# fen.net
KiCad netlist of a schematic drawn in EAGLE
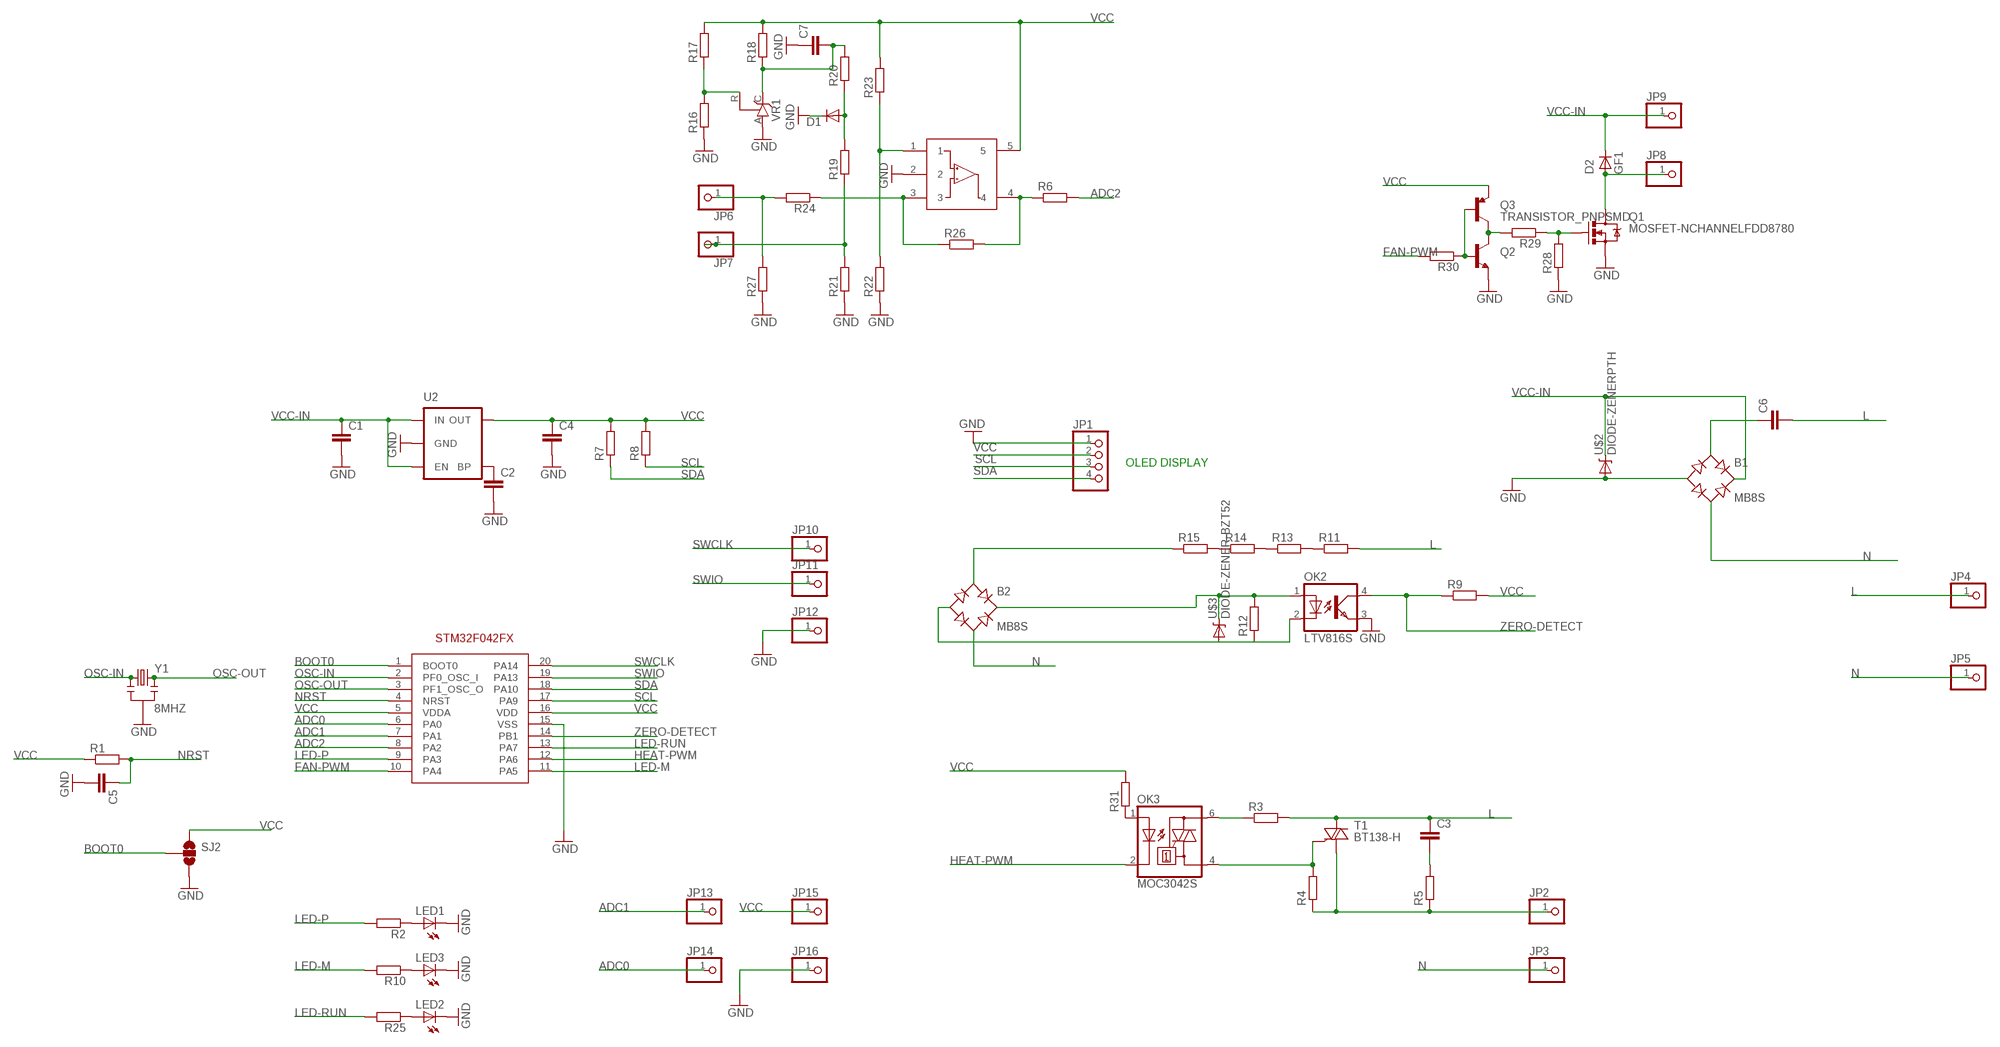
[diagram p0: schematic, sheet 1]

(export (version "E")
  (design (tool "Eeschema 10.0.6"))
  (components
    (comp (ref "B1")
      (value "MB8S")
      (footprint "eagle-import:SOIC-4")
      (libsource (lib "eagle-import") (part "MBS8"))
    )
    (comp (ref "B2")
      (value "MB8S")
      (footprint "eagle-import:SOIC-4")
      (libsource (lib "eagle-import") (part "MBS8"))
    )
    (comp (ref "C1")
      (value "C-EUC0805")
      (footprint "eagle-import:C0805")
      (libsource (lib "eagle-import") (part "C-EUC0805"))
    )
    (comp (ref "C2")
      (value "C-EUC0603")
      (footprint "eagle-import:C0603")
      (libsource (lib "eagle-import") (part "C-EUC0603"))
    )
    (comp (ref "C3")
      (value "C-EUC1206")
      (footprint "eagle-import:C1206")
      (libsource (lib "eagle-import") (part "C-EUC1206"))
    )
    (comp (ref "C4")
      (value "C-EUC0805")
      (footprint "eagle-import:C0805")
      (libsource (lib "eagle-import") (part "C-EUC0805"))
    )
    (comp (ref "C5")
      (value "C-EUC0603")
      (footprint "eagle-import:C0603")
      (libsource (lib "eagle-import") (part "C-EUC0603"))
    )
    (comp (ref "C6")
      (value "C-EU150-072X183")
      (footprint "eagle-import:C150-072X183")
      (libsource (lib "eagle-import") (part "C-EU150-072X183"))
    )
    (comp (ref "C7")
      (value "C-EUC0805")
      (footprint "eagle-import:C0805")
      (libsource (lib "eagle-import") (part "C-EUC0805"))
    )
    (comp (ref "D1")
      (value "DIODE1N4148")
      (footprint "eagle-import:DIODE-1N4148")
      (libsource (lib "eagle-import") (part "DIODE1N4148"))
    )
    (comp (ref "D2")
      (value "GF1")
      (footprint "eagle-import:SMA-DO214AC")
      (libsource (lib "eagle-import") (part "GF1"))
    )
    (comp (ref "JP1")
      (value "PINHD-1X4")
      (footprint "eagle-import:1X04")
      (libsource (lib "eagle-import") (part "PINHD-1X4"))
    )
    (comp (ref "JP2")
      (value "PINHD-1X1")
      (footprint "eagle-import:1X01")
      (libsource (lib "eagle-import") (part "PINHD-1X1"))
    )
    (comp (ref "JP3")
      (value "PINHD-1X1")
      (footprint "eagle-import:1X01")
      (libsource (lib "eagle-import") (part "PINHD-1X1"))
    )
    (comp (ref "JP4")
      (value "PINHD-1X1")
      (footprint "eagle-import:1X01")
      (libsource (lib "eagle-import") (part "PINHD-1X1"))
    )
    (comp (ref "JP5")
      (value "PINHD-1X1")
      (footprint "eagle-import:1X01")
      (libsource (lib "eagle-import") (part "PINHD-1X1"))
    )
    (comp (ref "JP6")
      (value "PINHD-1X1")
      (footprint "eagle-import:1X01")
      (libsource (lib "eagle-import") (part "PINHD-1X1"))
    )
    (comp (ref "JP7")
      (value "PINHD-1X1")
      (footprint "eagle-import:1X01")
      (libsource (lib "eagle-import") (part "PINHD-1X1"))
    )
    (comp (ref "JP8")
      (value "PINHD-1X1")
      (footprint "eagle-import:1X01")
      (libsource (lib "eagle-import") (part "PINHD-1X1"))
    )
    (comp (ref "JP9")
      (value "PINHD-1X1")
      (footprint "eagle-import:1X01")
      (libsource (lib "eagle-import") (part "PINHD-1X1"))
    )
    (comp (ref "JP10")
      (value "PINHD-1X1")
      (footprint "eagle-import:1X01")
      (libsource (lib "eagle-import") (part "PINHD-1X1"))
    )
    (comp (ref "JP11")
      (value "PINHD-1X1")
      (footprint "eagle-import:1X01")
      (libsource (lib "eagle-import") (part "PINHD-1X1"))
    )
    (comp (ref "JP12")
      (value "PINHD-1X1")
      (footprint "eagle-import:1X01")
      (libsource (lib "eagle-import") (part "PINHD-1X1"))
    )
    (comp (ref "JP13")
      (value "PINHD-1X1")
      (footprint "eagle-import:1X01")
      (libsource (lib "eagle-import") (part "PINHD-1X1"))
    )
    (comp (ref "JP14")
      (value "PINHD-1X1")
      (footprint "eagle-import:1X01")
      (libsource (lib "eagle-import") (part "PINHD-1X1"))
    )
    (comp (ref "JP15")
      (value "PINHD-1X1")
      (footprint "eagle-import:1X01")
      (libsource (lib "eagle-import") (part "PINHD-1X1"))
    )
    (comp (ref "JP16")
      (value "PINHD-1X1")
      (footprint "eagle-import:1X01")
      (libsource (lib "eagle-import") (part "PINHD-1X1"))
    )
    (comp (ref "LED1")
      (value "LED0603")
      (footprint "eagle-import:LED-0603")
      (libsource (lib "eagle-import") (part "LED0603"))
    )
    (comp (ref "LED2")
      (value "LED0603")
      (footprint "eagle-import:LED-0603")
      (libsource (lib "eagle-import") (part "LED0603"))
    )
    (comp (ref "LED3")
      (value "LED0603")
      (footprint "eagle-import:LED-0603")
      (libsource (lib "eagle-import") (part "LED0603"))
    )
    (comp (ref "OK2")
      (value "LTV816S")
      (footprint "eagle-import:SMD4")
      (libsource (lib "eagle-import") (part "LTV816S"))
    )
    (comp (ref "OK3")
      (value "MOC3042S")
      (footprint "eagle-import:DIL6-SMD")
      (fields (field (name "MF") "FAIRCHILD SEMICONDUCTOR") (field (name "MPN") "MOC3042SM"))
      (libsource (lib "eagle-import") (part "MOC30S42"))
    )
    (comp (ref "Q1")
      (value "MOSFET-NCHANNELFDD8780")
      (footprint "eagle-import:DPAK")
      (libsource (lib "eagle-import") (part "MOSFET-NCHANNELFDD8780"))
    )
    (comp (ref "Q2")
      (value "TRANSISTOR_NPNSOT23")
      (footprint "eagle-import:SOT23")
      (libsource (lib "eagle-import") (part "TRANSISTOR_NPNSOT23"))
    )
    (comp (ref "Q3")
      (value "TRANSISTOR_PNPSMD")
      (footprint "eagle-import:SOT23-3")
      (libsource (lib "eagle-import") (part "TRANSISTOR_PNPSMD"))
    )
    (comp (ref "R1")
      (value "R-EU_R0603")
      (footprint "eagle-import:R0603")
      (libsource (lib "eagle-import") (part "R-EU_R0603"))
    )
    (comp (ref "R2")
      (value "R-EU_R0603")
      (footprint "eagle-import:R0603")
      (libsource (lib "eagle-import") (part "R-EU_R0603"))
    )
    (comp (ref "R3")
      (value "R-EU_R1206")
      (footprint "eagle-import:R1206")
      (libsource (lib "eagle-import") (part "R-EU_R1206"))
    )
    (comp (ref "R4")
      (value "R-EU_R1206")
      (footprint "eagle-import:R1206")
      (libsource (lib "eagle-import") (part "R-EU_R1206"))
    )
    (comp (ref "R5")
      (value "R-EU_R1206")
      (footprint "eagle-import:R1206")
      (libsource (lib "eagle-import") (part "R-EU_R1206"))
    )
    (comp (ref "R6")
      (value "R-EU_R0603")
      (footprint "eagle-import:R0603")
      (libsource (lib "eagle-import") (part "R-EU_R0603"))
    )
    (comp (ref "R7")
      (value "R-EU_R0603")
      (footprint "eagle-import:R0603")
      (libsource (lib "eagle-import") (part "R-EU_R0603"))
    )
    (comp (ref "R8")
      (value "R-EU_R0603")
      (footprint "eagle-import:R0603")
      (libsource (lib "eagle-import") (part "R-EU_R0603"))
    )
    (comp (ref "R9")
      (value "R-EU_R0603")
      (footprint "eagle-import:R0603")
      (libsource (lib "eagle-import") (part "R-EU_R0603"))
    )
    (comp (ref "R10")
      (value "R-EU_R0603")
      (footprint "eagle-import:R0603")
      (libsource (lib "eagle-import") (part "R-EU_R0603"))
    )
    (comp (ref "R11")
      (value "R-EU_R1206")
      (footprint "eagle-import:R1206")
      (libsource (lib "eagle-import") (part "R-EU_R1206"))
    )
    (comp (ref "R12")
      (value "R-EU_R0603")
      (footprint "eagle-import:R0603")
      (libsource (lib "eagle-import") (part "R-EU_R0603"))
    )
    (comp (ref "R13")
      (value "R-EU_R1206")
      (footprint "eagle-import:R1206")
      (libsource (lib "eagle-import") (part "R-EU_R1206"))
    )
    (comp (ref "R14")
      (value "R-EU_R1206")
      (footprint "eagle-import:R1206")
      (libsource (lib "eagle-import") (part "R-EU_R1206"))
    )
    (comp (ref "R15")
      (value "R-EU_R1206")
      (footprint "eagle-import:R1206")
      (libsource (lib "eagle-import") (part "R-EU_R1206"))
    )
    (comp (ref "R16")
      (value "R-EU_R0603")
      (footprint "eagle-import:R0603")
      (libsource (lib "eagle-import") (part "R-EU_R0603"))
    )
    (comp (ref "R17")
      (value "R-EU_R0603")
      (footprint "eagle-import:R0603")
      (libsource (lib "eagle-import") (part "R-EU_R0603"))
    )
    (comp (ref "R18")
      (value "R-EU_R0603")
      (footprint "eagle-import:R0603")
      (libsource (lib "eagle-import") (part "R-EU_R0603"))
    )
    (comp (ref "R19")
      (value "R-EU_R0603")
      (footprint "eagle-import:R0603")
      (libsource (lib "eagle-import") (part "R-EU_R0603"))
    )
    (comp (ref "R20")
      (value "R-EU_R0603")
      (footprint "eagle-import:R0603")
      (libsource (lib "eagle-import") (part "R-EU_R0603"))
    )
    (comp (ref "R21")
      (value "R-EU_R0603")
      (footprint "eagle-import:R0603")
      (libsource (lib "eagle-import") (part "R-EU_R0603"))
    )
    (comp (ref "R22")
      (value "R-EU_R0603")
      (footprint "eagle-import:R0603")
      (libsource (lib "eagle-import") (part "R-EU_R0603"))
    )
    (comp (ref "R23")
      (value "R-EU_R0603")
      (footprint "eagle-import:R0603")
      (libsource (lib "eagle-import") (part "R-EU_R0603"))
    )
    (comp (ref "R24")
      (value "R-EU_R0603")
      (footprint "eagle-import:R0603")
      (libsource (lib "eagle-import") (part "R-EU_R0603"))
    )
    (comp (ref "R25")
      (value "R-EU_R0603")
      (footprint "eagle-import:R0603")
      (libsource (lib "eagle-import") (part "R-EU_R0603"))
    )
    (comp (ref "R26")
      (value "R-EU_R0603")
      (footprint "eagle-import:R0603")
      (libsource (lib "eagle-import") (part "R-EU_R0603"))
    )
    (comp (ref "R27")
      (value "R-EU_R0603")
      (footprint "eagle-import:R0603")
      (libsource (lib "eagle-import") (part "R-EU_R0603"))
    )
    (comp (ref "R28")
      (value "R-EU_R0603")
      (footprint "eagle-import:R0603")
      (libsource (lib "eagle-import") (part "R-EU_R0603"))
    )
    (comp (ref "R29")
      (value "R-EU_R0603")
      (footprint "eagle-import:R0603")
      (libsource (lib "eagle-import") (part "R-EU_R0603"))
    )
    (comp (ref "R30")
      (value "R-EU_R0603")
      (footprint "eagle-import:R0603")
      (libsource (lib "eagle-import") (part "R-EU_R0603"))
    )
    (comp (ref "R31")
      (value "R-EU_R0603")
      (footprint "eagle-import:R0603")
      (libsource (lib "eagle-import") (part "R-EU_R0603"))
    )
    (comp (ref "SJ2")
      (value "SOLDERJUMPER_2WAYS")
      (footprint "eagle-import:SJ_3")
      (libsource (lib "eagle-import") (part "SOLDERJUMPER_2WAYS"))
    )
    (comp (ref "T1")
      (value "BT138-H")
      (footprint "eagle-import:TO220BH")
      (libsource (lib "eagle-import") (part "BT138-H"))
    )
    (comp (ref "U$1")
      (value "LMV321M5")
      (footprint "eagle-import:SOT23-5")
      (libsource (lib "eagle-import") (part "LMV321M5"))
    )
    (comp (ref "U$2")
      (value "DIODE-ZENERPTH")
      (footprint "eagle-import:DIODE-ZENER")
      (libsource (lib "eagle-import") (part "DIODE-ZENERPTH"))
    )
    (comp (ref "U$3")
      (value "DIODE-ZENER-BZT52")
      (footprint "eagle-import:SOD-323")
      (libsource (lib "eagle-import") (part "DIODE-ZENER-BZT52"))
    )
    (comp (ref "U1")
      (value "STM32F042FX")
      (footprint "eagle-import:TSSOP20")
      (libsource (lib "eagle-import") (part "STM32F042FX"))
    )
    (comp (ref "U2")
      (value "MIC52053.3V")
      (footprint "eagle-import:SOT23-5")
      (libsource (lib "eagle-import") (part "MIC52053.3V"))
    )
    (comp (ref "VR1")
      (value "TL431CLP")
      (footprint "eagle-import:TO92-CLP")
      (libsource (lib "eagle-import") (part "TL431CLP"))
    )
    (comp (ref "Y1")
      (value "8MHZ")
      (footprint "eagle-import:RESONATOR-SMD")
      (libsource (lib "eagle-import") (part "RESONATOR8MHZ"))
    )
  )
  (nets
    (net (code "1") (name "/ADC0") (class "Default")
      (node (ref "JP14") (pin "1") (pinfunction "1_1") (pintype "passive"))
      (node (ref "U1") (pin "6") (pinfunction "PA0_6") (pintype "bidirectional"))
    )
    (net (code "2") (name "/ADC1") (class "Default")
      (node (ref "JP13") (pin "1") (pinfunction "1_1") (pintype "passive"))
      (node (ref "U1") (pin "7") (pinfunction "PA1_7") (pintype "bidirectional"))
    )
    (net (code "3") (name "/ADC2") (class "Default")
      (node (ref "R6") (pin "2") (pinfunction "2_2") (pintype "passive"))
      (node (ref "U1") (pin "8") (pinfunction "PA2_8") (pintype "bidirectional"))
    )
    (net (code "4") (name "/BOOT0") (class "Default")
      (node (ref "SJ2") (pin "2") (pinfunction "2_2") (pintype "passive"))
      (node (ref "U1") (pin "1") (pinfunction "BOOT0_1") (pintype "bidirectional"))
    )
    (net (code "5") (name "/FAN-PWM") (class "Default")
      (node (ref "R30") (pin "2") (pinfunction "2_2") (pintype "passive"))
      (node (ref "U1") (pin "10") (pinfunction "PA4_10") (pintype "bidirectional"))
    )
    (net (code "6") (name "/HEAT-PWM") (class "Default")
      (node (ref "OK3") (pin "2") (pinfunction "C_2") (pintype "passive"))
      (node (ref "U1") (pin "12") (pinfunction "PA6_12") (pintype "bidirectional"))
    )
    (net (code "7") (name "/L") (class "Default")
      (node (ref "C3") (pin "1") (pinfunction "1_1") (pintype "passive"))
      (node (ref "C6") (pin "2") (pinfunction "2_2") (pintype "passive"))
      (node (ref "JP4") (pin "1") (pinfunction "1_1") (pintype "passive"))
      (node (ref "R11") (pin "2") (pinfunction "2_2") (pintype "passive"))
      (node (ref "R3") (pin "2") (pinfunction "2_2") (pintype "passive"))
      (node (ref "T1") (pin "T2") (pinfunction "A2_T2") (pintype "passive"))
    )
    (net (code "8") (name "/LED-M") (class "Default")
      (node (ref "R10") (pin "2") (pinfunction "2_2") (pintype "passive"))
      (node (ref "U1") (pin "11") (pinfunction "PA5_11") (pintype "bidirectional"))
    )
    (net (code "9") (name "/LED-P") (class "Default")
      (node (ref "R2") (pin "2") (pinfunction "2_2") (pintype "passive"))
      (node (ref "U1") (pin "9") (pinfunction "PA3_9") (pintype "bidirectional"))
    )
    (net (code "10") (name "/LED-RUN") (class "Default")
      (node (ref "R25") (pin "2") (pinfunction "2_2") (pintype "passive"))
      (node (ref "U1") (pin "13") (pinfunction "PA7_13") (pintype "bidirectional"))
    )
    (net (code "11") (name "/N") (class "Default")
      (node (ref "B1") (pin "~2") (pinfunction "AC2_~2") (pintype "passive"))
      (node (ref "B2") (pin "~2") (pinfunction "AC2_~2") (pintype "passive"))
      (node (ref "JP3") (pin "1") (pinfunction "1_1") (pintype "passive"))
      (node (ref "JP5") (pin "1") (pinfunction "1_1") (pintype "passive"))
    )
    (net (code "12") (name "/NRST") (class "Default")
      (node (ref "C5") (pin "1") (pinfunction "1_1") (pintype "passive"))
      (node (ref "R1") (pin "2") (pinfunction "2_2") (pintype "passive"))
      (node (ref "U1") (pin "4") (pinfunction "NRST_4") (pintype "input"))
    )
    (net (code "13") (name "/OSC-IN") (class "Default")
      (node (ref "U1") (pin "2") (pinfunction "PF0_OSC_I_2") (pintype "bidirectional"))
      (node (ref "Y1") (pin "1") (pinfunction "1_1") (pintype "passive"))
    )
    (net (code "14") (name "/OSC-OUT") (class "Default")
      (node (ref "U1") (pin "3") (pinfunction "PF1_OSC_O_3") (pintype "bidirectional"))
      (node (ref "Y1") (pin "3") (pinfunction "3_3") (pintype "passive"))
    )
    (net (code "15") (name "/SCL") (class "Default")
      (node (ref "JP1") (pin "3") (pinfunction "3_3") (pintype "passive"))
      (node (ref "R8") (pin "1") (pinfunction "1_1") (pintype "passive"))
      (node (ref "U1") (pin "17") (pinfunction "PA9_17") (pintype "bidirectional"))
    )
    (net (code "16") (name "/SDA") (class "Default")
      (node (ref "JP1") (pin "4") (pinfunction "4_4") (pintype "passive"))
      (node (ref "R7") (pin "1") (pinfunction "1_1") (pintype "passive"))
      (node (ref "U1") (pin "18") (pinfunction "PA10_18") (pintype "bidirectional"))
    )
    (net (code "17") (name "/SWCLK") (class "Default")
      (node (ref "JP10") (pin "1") (pinfunction "1_1") (pintype "passive"))
      (node (ref "U1") (pin "20") (pinfunction "PA14_20") (pintype "bidirectional"))
    )
    (net (code "18") (name "/SWIO") (class "Default")
      (node (ref "JP11") (pin "1") (pinfunction "1_1") (pintype "passive"))
      (node (ref "U1") (pin "19") (pinfunction "PA13_19") (pintype "bidirectional"))
    )
    (net (code "19") (name "/VCC") (class "Default")
      (node (ref "C4") (pin "1") (pinfunction "1_1") (pintype "passive"))
      (node (ref "JP1") (pin "2") (pinfunction "2_2") (pintype "passive"))
      (node (ref "JP15") (pin "1") (pinfunction "1_1") (pintype "passive"))
      (node (ref "Q3") (pin "2") (pinfunction "E_2") (pintype "passive"))
      (node (ref "R1") (pin "1") (pinfunction "1_1") (pintype "passive"))
      (node (ref "R17") (pin "2") (pinfunction "2_2") (pintype "passive"))
      (node (ref "R18") (pin "2") (pinfunction "2_2") (pintype "passive"))
      (node (ref "R23") (pin "2") (pinfunction "2_2") (pintype "passive"))
      (node (ref "R31") (pin "2") (pinfunction "2_2") (pintype "passive"))
      (node (ref "R7") (pin "2") (pinfunction "2_2") (pintype "passive"))
      (node (ref "R8") (pin "2") (pinfunction "2_2") (pintype "passive"))
      (node (ref "R9") (pin "2") (pinfunction "2_2") (pintype "passive"))
      (node (ref "SJ2") (pin "1") (pinfunction "1_1") (pintype "passive"))
      (node (ref "U$1") (pin "5") (pinfunction "5_5") (pintype "bidirectional"))
      (node (ref "U1") (pin "16") (pinfunction "VDD_16") (pintype "power_in"))
      (node (ref "U1") (pin "5") (pinfunction "VDDA_5") (pintype "power_in"))
      (node (ref "U2") (pin "5") (pinfunction "OUT_5") (pintype "passive"))
    )
    (net (code "20") (name "/VCC-IN") (class "Default")
      (node (ref "B1") (pin "+") (pinfunction "+_+") (pintype "passive"))
      (node (ref "C1") (pin "1") (pinfunction "1_1") (pintype "passive"))
      (node (ref "D2") (pin "K") (pinfunction "C_K") (pintype "passive"))
      (node (ref "JP9") (pin "1") (pinfunction "1_1") (pintype "passive"))
      (node (ref "U$2") (pin "P$1") (pinfunction "C_P$1") (pintype "passive"))
      (node (ref "U2") (pin "1") (pinfunction "IN_1") (pintype "input"))
      (node (ref "U2") (pin "3") (pinfunction "EN_3") (pintype "input"))
    )
    (net (code "21") (name "/ZERO-DETECT") (class "Default")
      (node (ref "OK2") (pin "4") (pinfunction "COL_4") (pintype "passive"))
      (node (ref "R9") (pin "1") (pinfunction "1_1") (pintype "passive"))
      (node (ref "U1") (pin "14") (pinfunction "PB1_14") (pintype "bidirectional"))
    )
    (net (code "22") (name "GND") (class "Default")
      (node (ref "B1") (pin "-") (pinfunction "-_-") (pintype "passive"))
      (node (ref "C1") (pin "2") (pinfunction "2_2") (pintype "passive"))
      (node (ref "C2") (pin "2") (pinfunction "2_2") (pintype "passive"))
      (node (ref "C4") (pin "2") (pinfunction "2_2") (pintype "passive"))
      (node (ref "C5") (pin "2") (pinfunction "2_2") (pintype "passive"))
      (node (ref "C7") (pin "1") (pinfunction "1_1") (pintype "passive"))
      (node (ref "D1") (pin "C") (pinfunction "C_C") (pintype "passive"))
      (node (ref "JP1") (pin "1") (pinfunction "1_1") (pintype "passive"))
      (node (ref "JP12") (pin "1") (pinfunction "1_1") (pintype "passive"))
      (node (ref "JP16") (pin "1") (pinfunction "1_1") (pintype "passive"))
      (node (ref "LED1") (pin "C") (pinfunction "C_C") (pintype "passive"))
      (node (ref "LED2") (pin "C") (pinfunction "C_C") (pintype "passive"))
      (node (ref "LED3") (pin "C") (pinfunction "C_C") (pintype "passive"))
      (node (ref "OK2") (pin "3") (pinfunction "EMIT_3") (pintype "passive"))
      (node (ref "Q1") (pin "3") (pinfunction "S_3") (pintype "passive"))
      (node (ref "Q2") (pin "2") (pinfunction "E_2") (pintype "passive"))
      (node (ref "R16") (pin "1") (pinfunction "1_1") (pintype "passive"))
      (node (ref "R21") (pin "1") (pinfunction "1_1") (pintype "passive"))
      (node (ref "R22") (pin "1") (pinfunction "1_1") (pintype "passive"))
      (node (ref "R27") (pin "1") (pinfunction "1_1") (pintype "passive"))
      (node (ref "R28") (pin "1") (pinfunction "1_1") (pintype "passive"))
      (node (ref "SJ2") (pin "3") (pinfunction "3_3") (pintype "passive"))
      (node (ref "U$1") (pin "2") (pinfunction "2_2") (pintype "bidirectional"))
      (node (ref "U$2") (pin "P$2") (pinfunction "A_P$2") (pintype "passive"))
      (node (ref "U1") (pin "15") (pinfunction "VSS_15") (pintype "power_in"))
      (node (ref "U2") (pin "2") (pinfunction "GND_2") (pintype "input"))
      (node (ref "VR1") (pin "A") (pinfunction "A_A") (pintype "passive"))
      (node (ref "Y1") (pin "2") (pinfunction "2_2") (pintype "passive"))
    )
    (net (code "23") (name "Net-(B1-AC1)") (class "Default")
      (node (ref "B1") (pin "~1") (pinfunction "AC1_~1") (pintype "passive"))
      (node (ref "C6") (pin "1") (pinfunction "1_1") (pintype "passive"))
    )
    (net (code "24") (name "Net-(B2-AC1)") (class "Default")
      (node (ref "B2") (pin "~1") (pinfunction "AC1_~1") (pintype "passive"))
      (node (ref "R15") (pin "1") (pinfunction "1_1") (pintype "passive"))
    )
    (net (code "25") (name "Net-(C3-Pad2)") (class "Default")
      (node (ref "C3") (pin "2") (pinfunction "2_2") (pintype "passive"))
      (node (ref "R5") (pin "2") (pinfunction "2_2") (pintype "passive"))
    )
    (net (code "26") (name "Net-(C7-Pad2)") (class "Default")
      (node (ref "C7") (pin "2") (pinfunction "2_2") (pintype "passive"))
      (node (ref "R18") (pin "1") (pinfunction "1_1") (pintype "passive"))
      (node (ref "R20") (pin "2") (pinfunction "2_2") (pintype "passive"))
      (node (ref "VR1") (pin "C") (pinfunction "C_C") (pintype "passive"))
    )
    (net (code "27") (name "Net-(D1-PadA)") (class "Default")
      (node (ref "D1") (pin "A") (pinfunction "A_A") (pintype "passive"))
      (node (ref "R19") (pin "2") (pinfunction "2_2") (pintype "passive"))
      (node (ref "R20") (pin "1") (pinfunction "1_1") (pintype "passive"))
    )
    (net (code "28") (name "Net-(JP6-Pad1)") (class "Default")
      (node (ref "JP6") (pin "1") (pinfunction "1_1") (pintype "passive"))
      (node (ref "R24") (pin "2") (pinfunction "2_2") (pintype "passive"))
      (node (ref "R27") (pin "2") (pinfunction "2_2") (pintype "passive"))
    )
    (net (code "29") (name "Net-(JP7-Pad1)") (class "Default")
      (node (ref "JP7") (pin "1") (pinfunction "1_1") (pintype "passive"))
      (node (ref "R19") (pin "1") (pinfunction "1_1") (pintype "passive"))
      (node (ref "R21") (pin "2") (pinfunction "2_2") (pintype "passive"))
    )
    (net (code "30") (name "Net-(LED1-PadA)") (class "Default")
      (node (ref "LED1") (pin "A") (pinfunction "A_A") (pintype "passive"))
      (node (ref "R2") (pin "1") (pinfunction "1_1") (pintype "passive"))
    )
    (net (code "31") (name "Net-(LED2-PadA)") (class "Default")
      (node (ref "LED2") (pin "A") (pinfunction "A_A") (pintype "passive"))
      (node (ref "R25") (pin "1") (pinfunction "1_1") (pintype "passive"))
    )
    (net (code "32") (name "Net-(LED3-PadA)") (class "Default")
      (node (ref "LED3") (pin "A") (pinfunction "A_A") (pintype "passive"))
      (node (ref "R10") (pin "1") (pinfunction "1_1") (pintype "passive"))
    )
    (net (code "33") (name "Net-(OK2-A)") (class "Default")
      (node (ref "B2") (pin "+") (pinfunction "+_+") (pintype "passive"))
      (node (ref "OK2") (pin "1") (pinfunction "A_1") (pintype "passive"))
      (node (ref "R12") (pin "2") (pinfunction "2_2") (pintype "passive"))
      (node (ref "U$3") (pin "1") (pinfunction "C_1") (pintype "passive"))
    )
    (net (code "34") (name "Net-(OK2-C)") (class "Default")
      (node (ref "B2") (pin "-") (pinfunction "-_-") (pintype "passive"))
      (node (ref "OK2") (pin "2") (pinfunction "C_2") (pintype "passive"))
      (node (ref "R12") (pin "1") (pinfunction "1_1") (pintype "passive"))
      (node (ref "U$3") (pin "2") (pinfunction "A_2") (pintype "passive"))
    )
    (net (code "35") (name "Net-(OK3-A)") (class "Default")
      (node (ref "OK3") (pin "1") (pinfunction "A_1") (pintype "passive"))
      (node (ref "R31") (pin "1") (pinfunction "1_1") (pintype "passive"))
    )
    (net (code "36") (name "Net-(OK3-A1)") (class "Default")
      (node (ref "OK3") (pin "4") (pinfunction "A1_4") (pintype "passive"))
      (node (ref "R4") (pin "2") (pinfunction "2_2") (pintype "passive"))
      (node (ref "T1") (pin "G") (pinfunction "G_G") (pintype "passive"))
    )
    (net (code "37") (name "Net-(OK3-A2)") (class "Default")
      (node (ref "OK3") (pin "6") (pinfunction "A2_6") (pintype "passive"))
      (node (ref "R3") (pin "1") (pinfunction "1_1") (pintype "passive"))
    )
    (net (code "38") (name "Net-(Q1-D)") (class "Default")
      (node (ref "D2") (pin "A") (pinfunction "A_A") (pintype "passive"))
      (node (ref "JP8") (pin "1") (pinfunction "1_1") (pintype "passive"))
      (node (ref "Q1") (pin "4") (pinfunction "D_4") (pintype "passive"))
    )
    (net (code "39") (name "Net-(Q1-G)") (class "Default")
      (node (ref "Q1") (pin "1") (pinfunction "G_1") (pintype "passive"))
      (node (ref "R28") (pin "2") (pinfunction "2_2") (pintype "passive"))
      (node (ref "R29") (pin "1") (pinfunction "1_1") (pintype "passive"))
    )
    (net (code "40") (name "Net-(Q2-B)") (class "Default")
      (node (ref "Q2") (pin "1") (pinfunction "B_1") (pintype "passive"))
      (node (ref "Q3") (pin "1") (pinfunction "B_1") (pintype "passive"))
      (node (ref "R30") (pin "1") (pinfunction "1_1") (pintype "passive"))
    )
    (net (code "41") (name "Net-(Q2-C)") (class "Default")
      (node (ref "Q2") (pin "3") (pinfunction "C_3") (pintype "passive"))
      (node (ref "Q3") (pin "3") (pinfunction "C_3") (pintype "passive"))
      (node (ref "R29") (pin "2") (pinfunction "2_2") (pintype "passive"))
    )
    (net (code "42") (name "Net-(R11-Pad1)") (class "Default")
      (node (ref "R11") (pin "1") (pinfunction "1_1") (pintype "passive"))
      (node (ref "R13") (pin "2") (pinfunction "2_2") (pintype "passive"))
    )
    (net (code "43") (name "Net-(R13-Pad1)") (class "Default")
      (node (ref "R13") (pin "1") (pinfunction "1_1") (pintype "passive"))
      (node (ref "R14") (pin "2") (pinfunction "2_2") (pintype "passive"))
    )
    (net (code "44") (name "Net-(R14-Pad1)") (class "Default")
      (node (ref "R14") (pin "1") (pinfunction "1_1") (pintype "passive"))
      (node (ref "R15") (pin "2") (pinfunction "2_2") (pintype "passive"))
    )
    (net (code "45") (name "Net-(R16-Pad2)") (class "Default")
      (node (ref "R16") (pin "2") (pinfunction "2_2") (pintype "passive"))
      (node (ref "R17") (pin "1") (pinfunction "1_1") (pintype "passive"))
      (node (ref "VR1") (pin "R") (pinfunction "R_R") (pintype "passive"))
    )
    (net (code "46") (name "Net-(R22-Pad2)") (class "Default")
      (node (ref "R22") (pin "2") (pinfunction "2_2") (pintype "passive"))
      (node (ref "R23") (pin "1") (pinfunction "1_1") (pintype "passive"))
      (node (ref "U$1") (pin "1") (pinfunction "1_1") (pintype "bidirectional"))
    )
    (net (code "47") (name "Net-(R24-Pad1)") (class "Default")
      (node (ref "R24") (pin "1") (pinfunction "1_1") (pintype "passive"))
      (node (ref "R26") (pin "1") (pinfunction "1_1") (pintype "passive"))
      (node (ref "U$1") (pin "3") (pinfunction "3_3") (pintype "bidirectional"))
    )
    (net (code "48") (name "Net-(R26-Pad2)") (class "Default")
      (node (ref "R26") (pin "2") (pinfunction "2_2") (pintype "passive"))
      (node (ref "R6") (pin "1") (pinfunction "1_1") (pintype "passive"))
      (node (ref "U$1") (pin "4") (pinfunction "4_4") (pintype "bidirectional"))
    )
    (net (code "49") (name "Net-(T1-A1)") (class "Default")
      (node (ref "JP2") (pin "1") (pinfunction "1_1") (pintype "passive"))
      (node (ref "R4") (pin "1") (pinfunction "1_1") (pintype "passive"))
      (node (ref "R5") (pin "1") (pinfunction "1_1") (pintype "passive"))
      (node (ref "T1") (pin "T1") (pinfunction "A1_T1") (pintype "passive"))
    )
    (net (code "50") (name "Net-(U2-BP)") (class "Default")
      (node (ref "C2") (pin "1") (pinfunction "1_1") (pintype "passive"))
      (node (ref "U2") (pin "4") (pinfunction "BP_4") (pintype "input"))
    )
  )
)
